# C210_0001_Serial_Interface_220601.net
KiCad netlist of a schematic drawn in Altium Designer
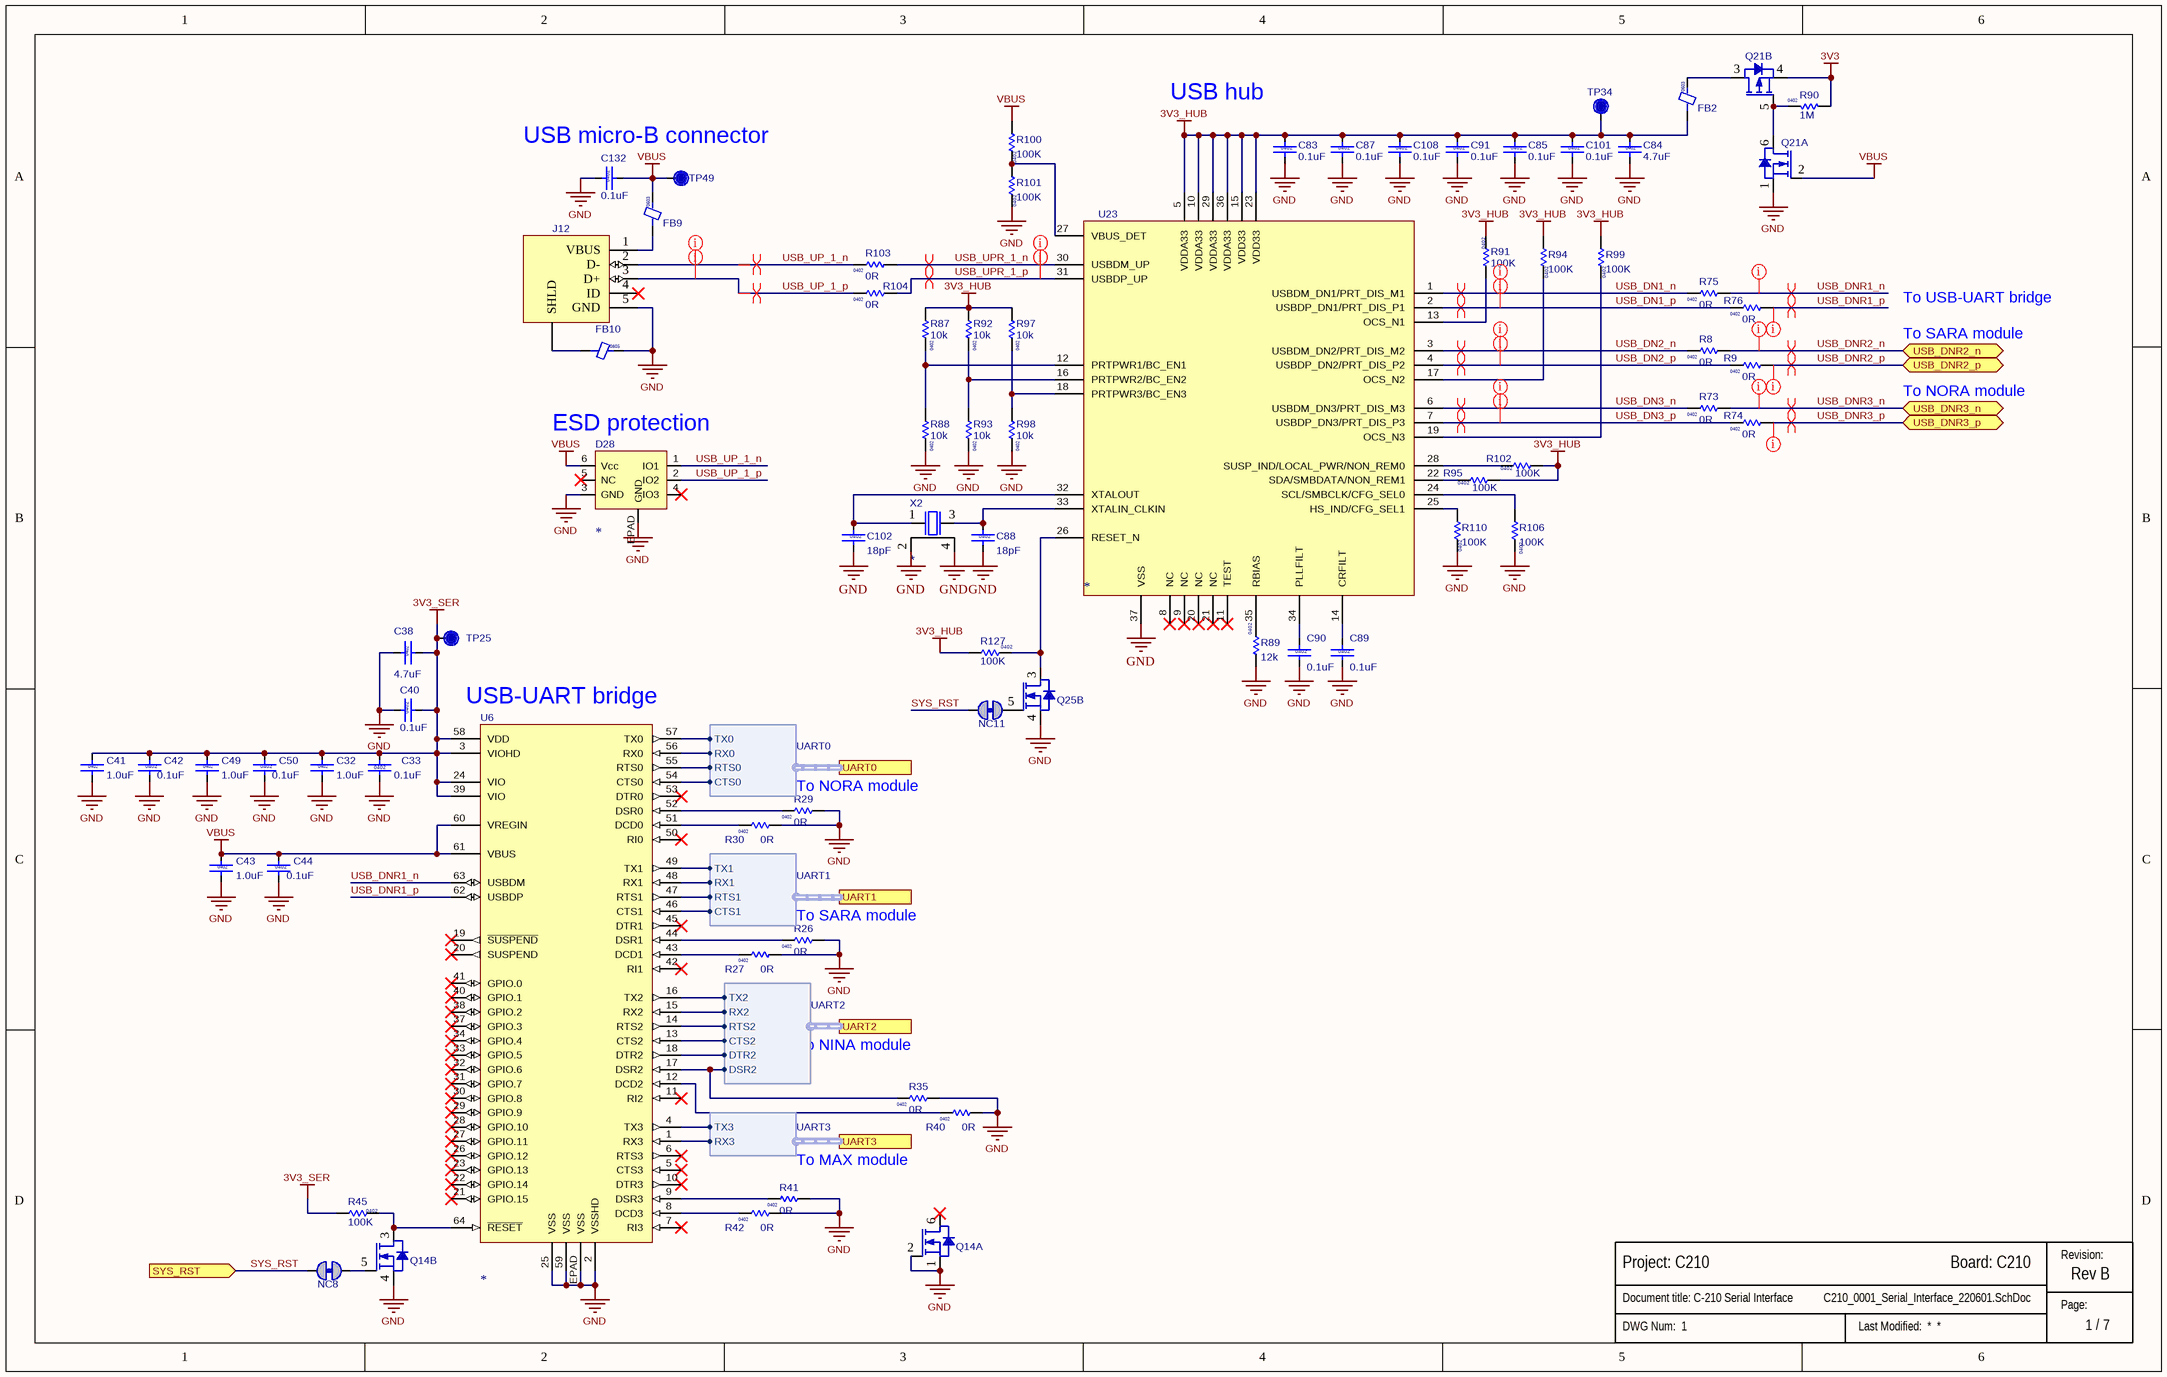
[diagram p0: C210_0001_Serial_Interface_220601.SchDoc]

(export (version "E")
  (design (tool "Eeschema 10.0.6"))
  (components
    (comp (ref "C32")
      (value "1.0uF")
      (footprint "Cap 0402 HD")
      (description "Cap, Ceramic, 1.0uF 10V 10% X5R, 0402")
      (fields
        (field (name "SIZE") "0402")
        (field (name "PART NUMBER") "120-00017")
        (field (name "MANUFACTURER") "Murata Electronics North America")
      )
      (libsource (lib "Arena_Parts_DB_Lib") (part "Cap Chip"))
    )
    (comp (ref "C33")
      (value "0.1uF")
      (footprint "Cap 0402 HD")
      (description "Cap, Ceramic 0.1uF 10V 10% X5R 0402")
      (fields
        (field (name "SIZE") "0402")
        (field (name "PART NUMBER") "120-00016")
        (field (name "MANUFACTURER") "Murata Electronics North America")
      )
      (libsource (lib "Arena_Parts_DB_Lib") (part "Cap Chip"))
    )
    (comp (ref "C38")
      (value "4.7uF")
      (footprint "Cap 0402 HD")
      (description "Cap, Ceramic 4.7uF 10V 20% X5R 0402")
      (fields
        (field (name "SIZE") "0402")
        (field (name "PART NUMBER") "120-00020")
        (field (name "TOLERANCE") "+/- 20%")
      )
      (libsource (lib "Arena_Parts_DB_Lib") (part "Cap Chip"))
    )
    (comp (ref "C40")
      (value "0.1uF")
      (footprint "Cap 0402 HD")
      (description "Cap, Ceramic 0.1uF 10V 10% X5R 0402")
      (fields
        (field (name "SIZE") "0402")
        (field (name "PART NUMBER") "120-00016")
        (field (name "MANUFACTURER") "Murata Electronics North America")
      )
      (libsource (lib "Arena_Parts_DB_Lib") (part "Cap Chip"))
    )
    (comp (ref "C41")
      (value "1.0uF")
      (footprint "Cap 0402 HD")
      (description "Cap, Ceramic, 1.0uF 10V 10% X5R, 0402")
      (fields
        (field (name "SIZE") "0402")
        (field (name "PART NUMBER") "120-00017")
        (field (name "MANUFACTURER") "Murata Electronics North America")
      )
      (libsource (lib "Arena_Parts_DB_Lib") (part "Cap Chip"))
    )
    (comp (ref "C42")
      (value "0.1uF")
      (footprint "Cap 0402 HD")
      (description "Cap, Ceramic 0.1uF 10V 10% X5R 0402")
      (fields
        (field (name "SIZE") "0402")
        (field (name "PART NUMBER") "120-00016")
        (field (name "MANUFACTURER") "Murata Electronics North America")
      )
      (libsource (lib "Arena_Parts_DB_Lib") (part "Cap Chip"))
    )
    (comp (ref "C43")
      (value "1.0uF")
      (footprint "Cap 0402 HD")
      (description "Cap, Ceramic, 1.0uF 10V 10% X5R, 0402")
      (fields
        (field (name "SIZE") "0402")
        (field (name "PART NUMBER") "120-00017")
        (field (name "MANUFACTURER") "Murata Electronics North America")
      )
      (libsource (lib "Arena_Parts_DB_Lib") (part "Cap Chip"))
    )
    (comp (ref "C44")
      (value "0.1uF")
      (footprint "Cap 0402 HD")
      (description "Cap, Ceramic 0.1uF 10V 10% X5R 0402")
      (fields
        (field (name "SIZE") "0402")
        (field (name "PART NUMBER") "120-00016")
        (field (name "MANUFACTURER") "Murata Electronics North America")
      )
      (libsource (lib "Arena_Parts_DB_Lib") (part "Cap Chip"))
    )
    (comp (ref "C49")
      (value "1.0uF")
      (footprint "Cap 0402 HD")
      (description "Cap, Ceramic, 1.0uF 10V 10% X5R, 0402")
      (fields
        (field (name "SIZE") "0402")
        (field (name "PART NUMBER") "120-00017")
        (field (name "MANUFACTURER") "Murata Electronics North America")
      )
      (libsource (lib "Arena_Parts_DB_Lib") (part "Cap Chip"))
    )
    (comp (ref "C50")
      (value "0.1uF")
      (footprint "Cap 0402 HD")
      (description "Cap, Ceramic 0.1uF 10V 10% X5R 0402")
      (fields
        (field (name "SIZE") "0402")
        (field (name "PART NUMBER") "120-00016")
        (field (name "MANUFACTURER") "Murata Electronics North America")
      )
      (libsource (lib "Arena_Parts_DB_Lib") (part "Cap Chip"))
    )
    (comp (ref "C83")
      (value "0.1uF")
      (footprint "Cap 0402 HD")
      (description "Cap, Ceramic 0.1uF 10V 10% X5R 0402")
      (fields
        (field (name "SIZE") "0402")
        (field (name "PART NUMBER") "120-00016")
        (field (name "MANUFACTURER") "Murata Electronics North America")
      )
      (libsource (lib "Arena_Parts_DB_Lib") (part "Cap Chip"))
    )
    (comp (ref "C84")
      (value "4.7uF")
      (footprint "Cap 0402 HD")
      (description "Cap, Ceramic 4.7uF 10V 20% X5R 0402")
      (fields
        (field (name "SIZE") "0402")
        (field (name "PART NUMBER") "120-00020")
        (field (name "TOLERANCE") "+/- 20%")
      )
      (libsource (lib "Arena_Parts_DB_Lib") (part "Cap Chip"))
    )
    (comp (ref "C85")
      (value "0.1uF")
      (footprint "Cap 0402 HD")
      (description "Cap, Ceramic 0.1uF 10V 10% X5R 0402")
      (fields
        (field (name "SIZE") "0402")
        (field (name "PART NUMBER") "120-00016")
        (field (name "MANUFACTURER") "Murata Electronics North America")
      )
      (libsource (lib "Arena_Parts_DB_Lib") (part "Cap Chip"))
    )
    (comp (ref "C87")
      (value "0.1uF")
      (footprint "Cap 0402 HD")
      (description "Cap, Ceramic 0.1uF 10V 10% X5R 0402")
      (fields
        (field (name "SIZE") "0402")
        (field (name "PART NUMBER") "120-00016")
        (field (name "MANUFACTURER") "Murata Electronics North America")
      )
      (libsource (lib "Arena_Parts_DB_Lib") (part "Cap Chip"))
    )
    (comp (ref "C88")
      (value "18pF")
      (footprint "Cap 0402 HD")
      (description "Cap, Ceramic 18pF 50V 5% NP0 0402")
      (fields
        (field (name "SIZE") "0402")
        (field (name "PART NUMBER") "120-00041")
        (field (name "TOLERANCE") "+/- 5%")
      )
      (libsource (lib "Arena_Parts_DB_Lib") (part "Cap Chip"))
    )
    (comp (ref "C89")
      (value "0.1uF")
      (footprint "Cap 0402 HD")
      (description "Cap, Ceramic 0.1uF 10V 10% X5R 0402")
      (fields
        (field (name "SIZE") "0402")
        (field (name "PART NUMBER") "120-00016")
        (field (name "MANUFACTURER") "Murata Electronics North America")
      )
      (libsource (lib "Arena_Parts_DB_Lib") (part "Cap Chip"))
    )
    (comp (ref "C90")
      (value "0.1uF")
      (footprint "Cap 0402 HD")
      (description "Cap, Ceramic 0.1uF 10V 10% X5R 0402")
      (fields
        (field (name "SIZE") "0402")
        (field (name "PART NUMBER") "120-00016")
        (field (name "MANUFACTURER") "Murata Electronics North America")
      )
      (libsource (lib "Arena_Parts_DB_Lib") (part "Cap Chip"))
    )
    (comp (ref "C91")
      (value "0.1uF")
      (footprint "Cap 0402 HD")
      (description "Cap, Ceramic 0.1uF 10V 10% X5R 0402")
      (fields
        (field (name "SIZE") "0402")
        (field (name "PART NUMBER") "120-00016")
        (field (name "MANUFACTURER") "Murata Electronics North America")
      )
      (libsource (lib "Arena_Parts_DB_Lib") (part "Cap Chip"))
    )
    (comp (ref "C101")
      (value "0.1uF")
      (footprint "Cap 0402 HD")
      (description "Cap, Ceramic 0.1uF 10V 10% X5R 0402")
      (fields
        (field (name "SIZE") "0402")
        (field (name "PART NUMBER") "120-00016")
        (field (name "MANUFACTURER") "Murata Electronics North America")
      )
      (libsource (lib "Arena_Parts_DB_Lib") (part "Cap Chip"))
    )
    (comp (ref "C102")
      (value "18pF")
      (footprint "Cap 0402 HD")
      (description "Cap, Ceramic 18pF 50V 5% NP0 0402")
      (fields
        (field (name "SIZE") "0402")
        (field (name "PART NUMBER") "120-00041")
        (field (name "TOLERANCE") "+/- 5%")
      )
      (libsource (lib "Arena_Parts_DB_Lib") (part "Cap Chip"))
    )
    (comp (ref "C108")
      (value "0.1uF")
      (footprint "Cap 0402 HD")
      (description "Cap, Ceramic 0.1uF 10V 10% X5R 0402")
      (fields
        (field (name "SIZE") "0402")
        (field (name "PART NUMBER") "120-00016")
        (field (name "MANUFACTURER") "Murata Electronics North America")
      )
      (libsource (lib "Arena_Parts_DB_Lib") (part "Cap Chip"))
    )
    (comp (ref "C132")
      (value "0.1uF")
      (footprint "Cap 0402 HD")
      (description "Cap, Ceramic 0.1uF 10V 10% X5R 0402")
      (fields
        (field (name "SIZE") "0402")
        (field (name "PART NUMBER") "120-00016")
        (field (name "MANUFACTURER") "Murata Electronics North America")
      )
      (libsource (lib "Arena_Parts_DB_Lib") (part "Cap Chip"))
    )
    (comp (ref "D28")
      (value "~")
      (footprint "TPD3E001DRSR")
      (description "TVS Diode, ESD High Speed 3-Channel Array, WSON-6, 3mmX3mm")
      (fields (field (name "VOLTAGE") "5.5V") (field (name "MANUFACTURER P/N") "*"))
      (libsource (lib "TPD3E001DRSR") (part "TPD3E001"))
    )
    (comp (ref "FB2")
      (value "BLM18EG221SN1")
      (footprint "BLM18EG221SN1")
      (description "Ferrite Bead, 220ohm @ 100MHz, 2A, 0603")
      (fields (field (name "VOLTAGE") "None") (field (name "SIZE") "0603"))
      (libsource (lib "BLM18EG221SN1") (part "BLM18EG221SN1"))
    )
    (comp (ref "FB9")
      (value "BLM18EG221SN1")
      (footprint "BLM18EG221SN1")
      (description "Ferrite Bead, 220ohm @ 100MHz, 2A, 0603")
      (fields (field (name "VOLTAGE") "None") (field (name "SIZE") "0603"))
      (libsource (lib "BLM18EG221SN1") (part "BLM18EG221SN1"))
    )
    (comp (ref "FB10")
      (value "155-00014")
      (footprint "IND 0805")
      (description "Ferrite Bead, 120ohm @ 100MHz, 3A, 0805")
      (fields (field (name "SIZE") "0805") (field (name "VOLTAGE") "None"))
      (libsource (lib "Arena_Parts_DB_Lib") (part "FB sm"))
    )
    (comp (ref "J12")
      (value "130-00008")
      (footprint "USB_Micro_RA_W-2TABS")
      (description "USB Micro B Receptacle, Right Angle SMT with 2 TH Tabs, 0.65mm")
      (fields (field (name "MANUFACTURER") "FCI"))
      (libsource (lib "Arena_Lib") (part "USB_W-Shield"))
    )
    (comp (ref "NC8")
      (value "Solderbridge-ShortDNP")
      (footprint "Solderbridge-Short")
      (description "Solderbridge-Short")
      (fields (field (name "ADDED BY") "Paul B"))
      (libsource (lib "PCB_Misc") (part "Solderbridge-Short"))
    )
    (comp (ref "NC11")
      (value "Solderbridge-ShortDNP")
      (footprint "Solderbridge-Short")
      (description "Solderbridge-Short")
      (fields (field (name "ADDED BY") "Paul B"))
      (libsource (lib "PCB_Misc") (part "Solderbridge-Short"))
    )
    (comp (ref "Q14")
      (value "140-00016")
      (footprint "SOT-563")
      (description "MOSFET 2N-CH 20V 0.8A, SOT-563")
      (fields (field (name "VOLTAGE") "20V"))
      (libsource (lib "Arena_Parts_DB_Lib") (part "MOSFET-N-Dual"))
    )
    (comp (ref "Q21")
      (value "140-00030")
      (footprint "SOT-563")
      (description "MOSFET N/P-CH 20V SOT-563, 540 mA, −430 mA")
      (fields (field (name "VOLTAGE") "20V"))
      (libsource (lib "Arena_Parts_DB_Lib") (part "MOSFET-N-P_Pair"))
    )
    (comp (ref "Q25")
      (value "140-00016")
      (footprint "SOT-563")
      (description "MOSFET 2N-CH 20V 0.8A, SOT-563")
      (fields (field (name "VOLTAGE") "20V"))
      (libsource (lib "Arena_Parts_DB_Lib") (part "MOSFET-N-Dual"))
    )
    (comp (ref "R8")
      (value "0R")
      (footprint "RES 0402 HD")
      (description "Resistor 0 ohm 1/16W 0402")
      (fields
        (field (name "SIZE") "0402")
        (field (name "PART NUMBER") "180-00020")
        (field (name "POWER") "1/16W")
      )
      (libsource (lib "Arena_Parts_DB_Lib") (part "Res sm"))
    )
    (comp (ref "R9")
      (value "0R")
      (footprint "RES 0402 HD")
      (description "Resistor 0 ohm 1/16W 0402")
      (fields
        (field (name "SIZE") "0402")
        (field (name "PART NUMBER") "180-00020")
        (field (name "POWER") "1/16W")
      )
      (libsource (lib "Arena_Parts_DB_Lib") (part "Res sm"))
    )
    (comp (ref "R26")
      (value "0R")
      (footprint "RES 0402 HD")
      (description "Resistor 0 ohm 1/16W 0402")
      (fields
        (field (name "SIZE") "0402")
        (field (name "PART NUMBER") "180-00020")
        (field (name "POWER") "1/16W")
      )
      (libsource (lib "Arena_Parts_DB_Lib") (part "Res sm"))
    )
    (comp (ref "R27")
      (value "0R")
      (footprint "RES 0402 HD")
      (description "Resistor 0 ohm 1/16W 0402")
      (fields
        (field (name "SIZE") "0402")
        (field (name "PART NUMBER") "180-00020")
        (field (name "POWER") "1/16W")
      )
      (libsource (lib "Arena_Parts_DB_Lib") (part "Res sm"))
    )
    (comp (ref "R29")
      (value "0R")
      (footprint "RES 0402 HD")
      (description "Resistor 0 ohm 1/16W 0402")
      (fields
        (field (name "SIZE") "0402")
        (field (name "PART NUMBER") "180-00020")
        (field (name "POWER") "1/16W")
      )
      (libsource (lib "Arena_Parts_DB_Lib") (part "Res sm"))
    )
    (comp (ref "R30")
      (value "0R")
      (footprint "RES 0402 HD")
      (description "Resistor 0 ohm 1/16W 0402")
      (fields
        (field (name "SIZE") "0402")
        (field (name "PART NUMBER") "180-00020")
        (field (name "POWER") "1/16W")
      )
      (libsource (lib "Arena_Parts_DB_Lib") (part "Res sm"))
    )
    (comp (ref "R35")
      (value "0R")
      (footprint "RES 0402 HD")
      (description "Resistor 0 ohm 1/16W 0402")
      (fields
        (field (name "SIZE") "0402")
        (field (name "PART NUMBER") "180-00020")
        (field (name "POWER") "1/16W")
      )
      (libsource (lib "Arena_Parts_DB_Lib") (part "Res sm"))
    )
    (comp (ref "R40")
      (value "0R")
      (footprint "RES 0402 HD")
      (description "Resistor 0 ohm 1/16W 0402")
      (fields
        (field (name "SIZE") "0402")
        (field (name "PART NUMBER") "180-00020")
        (field (name "POWER") "1/16W")
      )
      (libsource (lib "Arena_Parts_DB_Lib") (part "Res sm"))
    )
    (comp (ref "R41")
      (value "0R")
      (footprint "RES 0402 HD")
      (description "Resistor 0 ohm 1/16W 0402")
      (fields
        (field (name "SIZE") "0402")
        (field (name "PART NUMBER") "180-00020")
        (field (name "POWER") "1/16W")
      )
      (libsource (lib "Arena_Parts_DB_Lib") (part "Res sm"))
    )
    (comp (ref "R42")
      (value "0R")
      (footprint "RES 0402 HD")
      (description "Resistor 0 ohm 1/16W 0402")
      (fields
        (field (name "SIZE") "0402")
        (field (name "PART NUMBER") "180-00020")
        (field (name "POWER") "1/16W")
      )
      (libsource (lib "Arena_Parts_DB_Lib") (part "Res sm"))
    )
    (comp (ref "R45")
      (value "100K")
      (footprint "RES 0402 HD")
      (description "Resistor 100K ohm 1% 1/16W, 0402")
      (fields
        (field (name "SIZE") "0402")
        (field (name "PART NUMBER") "180-00093")
        (field (name "POWER") "1/16W")
      )
      (libsource (lib "Arena_Parts_DB_Lib") (part "Res sm"))
    )
    (comp (ref "R73")
      (value "0R")
      (footprint "RES 0402 HD")
      (description "Resistor 0 ohm 1/16W 0402")
      (fields
        (field (name "SIZE") "0402")
        (field (name "PART NUMBER") "180-00020")
        (field (name "POWER") "1/16W")
      )
      (libsource (lib "Arena_Parts_DB_Lib") (part "Res sm"))
    )
    (comp (ref "R74")
      (value "0R")
      (footprint "RES 0402 HD")
      (description "Resistor 0 ohm 1/16W 0402")
      (fields
        (field (name "SIZE") "0402")
        (field (name "PART NUMBER") "180-00020")
        (field (name "POWER") "1/16W")
      )
      (libsource (lib "Arena_Parts_DB_Lib") (part "Res sm"))
    )
    (comp (ref "R75")
      (value "0R")
      (footprint "RES 0402 HD")
      (description "Resistor 0 ohm 1/16W 0402")
      (fields
        (field (name "SIZE") "0402")
        (field (name "PART NUMBER") "180-00020")
        (field (name "POWER") "1/16W")
      )
      (libsource (lib "Arena_Parts_DB_Lib") (part "Res sm"))
    )
    (comp (ref "R76")
      (value "0R")
      (footprint "RES 0402 HD")
      (description "Resistor 0 ohm 1/16W 0402")
      (fields
        (field (name "SIZE") "0402")
        (field (name "PART NUMBER") "180-00020")
        (field (name "POWER") "1/16W")
      )
      (libsource (lib "Arena_Parts_DB_Lib") (part "Res sm"))
    )
    (comp (ref "R87")
      (value "10k")
      (footprint "RES 0402 HD")
      (description "Resistor 10k ohm 1% 1/16W, 0402")
      (fields
        (field (name "SIZE") "0402")
        (field (name "PART NUMBER") "180-00024")
        (field (name "POWER") "1/16W")
      )
      (libsource (lib "Arena_Parts_DB_Lib") (part "Res sm"))
    )
    (comp (ref "R88")
      (value "10k")
      (footprint "RES 0402 HD")
      (description "Resistor 10k ohm 1% 1/16W, 0402")
      (fields
        (field (name "SIZE") "0402")
        (field (name "PART NUMBER") "180-00024")
        (field (name "POWER") "1/16W")
      )
      (libsource (lib "Arena_Parts_DB_Lib") (part "Res sm"))
    )
    (comp (ref "R89")
      (value "12k")
      (footprint "RES 0402 HD")
      (description "Resistor 12k ohm 1% 1/16W 0402")
      (fields
        (field (name "SIZE") "0402")
        (field (name "PART NUMBER") "180-00096")
        (field (name "POWER") "1/16W")
      )
      (libsource (lib "Arena_Parts_DB_Lib") (part "Res sm"))
    )
    (comp (ref "R90")
      (value "1M")
      (footprint "RES 0402 HD")
      (description "Resistor 1M ohm 1%, 1/16W, 0402")
      (fields
        (field (name "SIZE") "0402")
        (field (name "PART NUMBER") "180-00054")
        (field (name "POWER") "1/16W")
      )
      (libsource (lib "Arena_Parts_DB_Lib") (part "Res sm"))
    )
    (comp (ref "R91")
      (value "100K")
      (footprint "RES 0402 HD")
      (description "Resistor 100K ohm 1% 1/16W, 0402")
      (fields
        (field (name "SIZE") "0402")
        (field (name "PART NUMBER") "180-00093")
        (field (name "POWER") "1/16W")
      )
      (libsource (lib "Arena_Parts_DB_Lib") (part "Res sm"))
    )
    (comp (ref "R92")
      (value "10k")
      (footprint "RES 0402 HD")
      (description "Resistor 10k ohm 1% 1/16W, 0402")
      (fields
        (field (name "SIZE") "0402")
        (field (name "PART NUMBER") "180-00024")
        (field (name "POWER") "1/16W")
      )
      (libsource (lib "Arena_Parts_DB_Lib") (part "Res sm"))
    )
    (comp (ref "R93")
      (value "10k")
      (footprint "RES 0402 HD")
      (description "Resistor 10k ohm 1% 1/16W, 0402")
      (fields
        (field (name "SIZE") "0402")
        (field (name "PART NUMBER") "180-00024")
        (field (name "POWER") "1/16W")
      )
      (libsource (lib "Arena_Parts_DB_Lib") (part "Res sm"))
    )
    (comp (ref "R94")
      (value "100K")
      (footprint "RES 0402 HD")
      (description "Resistor 100K ohm 1% 1/16W, 0402")
      (fields
        (field (name "SIZE") "0402")
        (field (name "PART NUMBER") "180-00093")
        (field (name "POWER") "1/16W")
      )
      (libsource (lib "Arena_Parts_DB_Lib") (part "Res sm"))
    )
    (comp (ref "R95")
      (value "100K")
      (footprint "RES 0402 HD")
      (description "Resistor 100K ohm 1% 1/16W, 0402")
      (fields
        (field (name "SIZE") "0402")
        (field (name "PART NUMBER") "180-00093")
        (field (name "POWER") "1/16W")
      )
      (libsource (lib "Arena_Parts_DB_Lib") (part "Res sm"))
    )
    (comp (ref "R97")
      (value "10k")
      (footprint "RES 0402 HD")
      (description "Resistor 10k ohm 1% 1/16W, 0402")
      (fields
        (field (name "SIZE") "0402")
        (field (name "PART NUMBER") "180-00024")
        (field (name "POWER") "1/16W")
      )
      (libsource (lib "Arena_Parts_DB_Lib") (part "Res sm"))
    )
    (comp (ref "R98")
      (value "10k")
      (footprint "RES 0402 HD")
      (description "Resistor 10k ohm 1% 1/16W, 0402")
      (fields
        (field (name "SIZE") "0402")
        (field (name "PART NUMBER") "180-00024")
        (field (name "POWER") "1/16W")
      )
      (libsource (lib "Arena_Parts_DB_Lib") (part "Res sm"))
    )
    (comp (ref "R99")
      (value "100K")
      (footprint "RES 0402 HD")
      (description "Resistor 100K ohm 1% 1/16W, 0402")
      (fields
        (field (name "SIZE") "0402")
        (field (name "PART NUMBER") "180-00093")
        (field (name "POWER") "1/16W")
      )
      (libsource (lib "Arena_Parts_DB_Lib") (part "Res sm"))
    )
    (comp (ref "R100")
      (value "100K")
      (footprint "RES 0402 HD")
      (description "Resistor 100K ohm 1% 1/16W, 0402")
      (fields
        (field (name "SIZE") "0402")
        (field (name "PART NUMBER") "180-00093")
        (field (name "POWER") "1/16W")
      )
      (libsource (lib "Arena_Parts_DB_Lib") (part "Res sm"))
    )
    (comp (ref "R101")
      (value "100K")
      (footprint "RES 0402 HD")
      (description "Resistor 100K ohm 1% 1/16W, 0402")
      (fields
        (field (name "SIZE") "0402")
        (field (name "PART NUMBER") "180-00093")
        (field (name "POWER") "1/16W")
      )
      (libsource (lib "Arena_Parts_DB_Lib") (part "Res sm"))
    )
    (comp (ref "R102")
      (value "100K")
      (footprint "RES 0402 HD")
      (description "Resistor 100K ohm 1% 1/16W, 0402")
      (fields
        (field (name "SIZE") "0402")
        (field (name "PART NUMBER") "180-00093")
        (field (name "POWER") "1/16W")
      )
      (libsource (lib "Arena_Parts_DB_Lib") (part "Res sm"))
    )
    (comp (ref "R103")
      (value "0R")
      (footprint "RES 0402 HD")
      (description "Resistor 0 ohm 1/16W 0402")
      (fields
        (field (name "SIZE") "0402")
        (field (name "PART NUMBER") "180-00020")
        (field (name "POWER") "1/16W")
      )
      (libsource (lib "Arena_Parts_DB_Lib") (part "Res sm"))
    )
    (comp (ref "R104")
      (value "0R")
      (footprint "RES 0402 HD")
      (description "Resistor 0 ohm 1/16W 0402")
      (fields
        (field (name "SIZE") "0402")
        (field (name "PART NUMBER") "180-00020")
        (field (name "POWER") "1/16W")
      )
      (libsource (lib "Arena_Parts_DB_Lib") (part "Res sm"))
    )
    (comp (ref "R106")
      (value "100K")
      (footprint "RES 0402 HD")
      (description "Resistor 100K ohm 1% 1/16W, 0402")
      (fields
        (field (name "SIZE") "0402")
        (field (name "PART NUMBER") "180-00093")
        (field (name "POWER") "1/16W")
      )
      (libsource (lib "Arena_Parts_DB_Lib") (part "Res sm"))
    )
    (comp (ref "R110")
      (value "100K")
      (footprint "RES 0402 HD")
      (description "Resistor 100K ohm 1% 1/16W, 0402")
      (fields
        (field (name "SIZE") "0402")
        (field (name "PART NUMBER") "180-00093")
        (field (name "POWER") "1/16W")
      )
      (libsource (lib "Arena_Parts_DB_Lib") (part "Res sm"))
    )
    (comp (ref "R127")
      (value "100K")
      (footprint "RES 0402 HD")
      (description "Resistor 100K ohm 1% 1/16W, 0402")
      (fields
        (field (name "SIZE") "0402")
        (field (name "PART NUMBER") "180-00093")
        (field (name "POWER") "1/16W")
      )
      (libsource (lib "Arena_Parts_DB_Lib") (part "Res sm"))
    )
    (comp (ref "TP25")
      (value "TP")
      (footprint "TP12R")
      (description "Testpoint, Round 1.0mm Dia")
      (fields
        (field (name "PART NUMBER") "TP10R")
        (field (name "ADDED BY") "Jeremy D")
        (field (name "CHECKED BY") "Paul B")
      )
      (libsource (lib "PCB_Misc") (part "TP_R"))
    )
    (comp (ref "TP34")
      (value "TP")
      (footprint "TP12R")
      (description "Testpoint, Round 1.0mm Dia")
      (fields
        (field (name "PART NUMBER") "TP10R")
        (field (name "ADDED BY") "Jeremy D")
        (field (name "CHECKED BY") "Paul B")
      )
      (libsource (lib "PCB_Misc") (part "TP_R"))
    )
    (comp (ref "TP49")
      (value "TP")
      (footprint "TP12R")
      (description "Testpoint, Round 1.0mm Dia")
      (fields
        (field (name "PART NUMBER") "TP10R")
        (field (name "ADDED BY") "Jeremy D")
        (field (name "CHECKED BY") "Paul B")
      )
      (libsource (lib "PCB_Misc") (part "TP_R"))
    )
    (comp (ref "U6")
      (value "220-00051")
      (footprint "QFN0.5P16x16-64Pin_W-Pad4.25mm")
      (description "IC BRIDGE USB TO UART 64QFN")
      (fields (field (name "MANUFACTURER P/N") "*") (field (name "VOLTAGE") "3.6V"))
      (libsource (lib "Arena_Parts_DB_Lib") (part "CP2108"))
    )
    (comp (ref "U23")
      (value "-\"Part Number\" + DNP")
      (footprint "QFN0.5P9x9-36Pin_W-PAD")
      (description "3-PORT USB 2.0 HUB CTRLR, QFN-36")
      (fields
        (field (name "MANUFACTURER P/N") "*")
        (field (name "PART NUMBER") "220-00017")
        (field (name "VOLTAGE") "3.6V")
      )
      (libsource (lib "Arena_Parts_DB_Lib") (part "USB2513B"))
    )
    (comp (ref "X2")
      (value "100-00017")
      (footprint "XTAL_2520_HD")
      (description "Crystal, 24.0000MHz, 20ppm, 10pF, 100 Ohm, -20Â°C - 70Â°C, SMT 4 Pin 2520")
      (fields (field (name "ALTIUM_VALUE") "*") (field (name "VOLTAGE") "None"))
      (libsource (lib "Arena_Parts_DB_Lib") (part "XTAL_4Pin"))
    )
  )
  (nets
    (net (code "5") (name "/CTS0") (class "Default")
      (node (ref "U6") (pin "54") (pinfunction "CTS0_54") (pintype "input"))
    )
    (net (code "6") (name "/CTS1") (class "Default")
      (node (ref "U6") (pin "46") (pinfunction "CTS1_46") (pintype "input"))
    )
    (net (code "7") (name "/CTS2") (class "Default")
      (node (ref "U6") (pin "13") (pinfunction "CTS2_13") (pintype "input"))
    )
    (net (code "8") (name "/DSR2") (class "Default")
      (node (ref "R35") (pin "2") (pinfunction "2_2") (pintype "passive"))
      (node (ref "U6") (pin "17") (pinfunction "DSR2_17") (pintype "input"))
    )
    (net (code "9") (name "/DTR2") (class "Default")
      (node (ref "U6") (pin "18") (pinfunction "DTR2_18") (pintype "output"))
    )
    (net (code "10") (name "/RTS0") (class "Default")
      (node (ref "U6") (pin "55") (pinfunction "RTS0_55") (pintype "output"))
    )
    (net (code "11") (name "/RTS1") (class "Default")
      (node (ref "U6") (pin "47") (pinfunction "RTS1_47") (pintype "output"))
    )
    (net (code "12") (name "/RTS2") (class "Default")
      (node (ref "U6") (pin "14") (pinfunction "RTS2_14") (pintype "output"))
    )
    (net (code "13") (name "/RX0") (class "Default")
      (node (ref "U6") (pin "56") (pinfunction "RX0_56") (pintype "input"))
    )
    (net (code "14") (name "/RX1") (class "Default")
      (node (ref "U6") (pin "48") (pinfunction "RX1_48") (pintype "input"))
    )
    (net (code "15") (name "/RX2") (class "Default")
      (node (ref "U6") (pin "15") (pinfunction "RX2_15") (pintype "input"))
    )
    (net (code "16") (name "/RX3") (class "Default")
      (node (ref "U6") (pin "1") (pinfunction "RX3_1") (pintype "input"))
    )
    (net (code "17") (name "/SYS_RST") (class "Default")
      (node (ref "NC11") (pin "2") (pinfunction "2_2") (pintype "passive"))
      (node (ref "NC8") (pin "2") (pinfunction "2_2") (pintype "passive"))
    )
    (net (code "18") (name "/TX0") (class "Default")
      (node (ref "U6") (pin "57") (pinfunction "TX0_57") (pintype "output"))
    )
    (net (code "19") (name "/TX1") (class "Default")
      (node (ref "U6") (pin "49") (pinfunction "TX1_49") (pintype "output"))
    )
    (net (code "20") (name "/TX2") (class "Default")
      (node (ref "U6") (pin "16") (pinfunction "TX2_16") (pintype "output"))
    )
    (net (code "21") (name "/TX3") (class "Default")
      (node (ref "U6") (pin "4") (pinfunction "TX3_4") (pintype "output"))
    )
    (net (code "22") (name "/USB_DN1_n") (class "Default")
      (node (ref "R75") (pin "2") (pinfunction "2_2") (pintype "passive"))
      (node (ref "U23") (pin "1") (pinfunction "USBDM_DN1/PRT_DIS_M1_1") (pintype "passive"))
    )
    (net (code "23") (name "/USB_DN1_p") (class "Default")
      (node (ref "R76") (pin "2") (pinfunction "2_2") (pintype "passive"))
      (node (ref "U23") (pin "2") (pinfunction "USBDP_DN1/PRT_DIS_P1_2") (pintype "passive"))
    )
    (net (code "24") (name "/USB_DN2_n") (class "Default")
      (node (ref "R8") (pin "2") (pinfunction "2_2") (pintype "passive"))
      (node (ref "U23") (pin "3") (pinfunction "USBDM_DN2/PRT_DIS_M2_3") (pintype "passive"))
    )
    (net (code "25") (name "/USB_DN2_p") (class "Default")
      (node (ref "R9") (pin "2") (pinfunction "2_2") (pintype "passive"))
      (node (ref "U23") (pin "4") (pinfunction "USBDP_DN2/PRT_DIS_P2_4") (pintype "passive"))
    )
    (net (code "26") (name "/USB_DN3_n") (class "Default")
      (node (ref "R73") (pin "2") (pinfunction "2_2") (pintype "passive"))
      (node (ref "U23") (pin "6") (pinfunction "USBDM_DN3/PRT_DIS_M3_6") (pintype "passive"))
    )
    (net (code "27") (name "/USB_DN3_p") (class "Default")
      (node (ref "R74") (pin "2") (pinfunction "2_2") (pintype "passive"))
      (node (ref "U23") (pin "7") (pinfunction "USBDP_DN3/PRT_DIS_P3_7") (pintype "passive"))
    )
    (net (code "28") (name "/USB_DNR1_n") (class "Default")
      (node (ref "R75") (pin "1") (pinfunction "1_1") (pintype "passive"))
      (node (ref "U6") (pin "63") (pinfunction "USBDM_63") (pintype "bidirectional"))
    )
    (net (code "29") (name "/USB_DNR1_p") (class "Default")
      (node (ref "R76") (pin "1") (pinfunction "1_1") (pintype "passive"))
      (node (ref "U6") (pin "62") (pinfunction "USBDP_62") (pintype "bidirectional"))
    )
    (net (code "30") (name "/USB_DNR2_n") (class "Default")
      (node (ref "R8") (pin "1") (pinfunction "1_1") (pintype "passive"))
    )
    (net (code "31") (name "/USB_DNR2_p") (class "Default")
      (node (ref "R9") (pin "1") (pinfunction "1_1") (pintype "passive"))
    )
    (net (code "32") (name "/USB_DNR3_n") (class "Default")
      (node (ref "R73") (pin "1") (pinfunction "1_1") (pintype "passive"))
    )
    (net (code "33") (name "/USB_DNR3_p") (class "Default")
      (node (ref "R74") (pin "1") (pinfunction "1_1") (pintype "passive"))
    )
    (net (code "34") (name "/USB_UPR_1_n") (class "Default")
      (node (ref "R103") (pin "1") (pinfunction "1_1") (pintype "passive"))
      (node (ref "U23") (pin "30") (pinfunction "USBDM_UP_30") (pintype "passive"))
    )
    (net (code "35") (name "/USB_UPR_1_p") (class "Default")
      (node (ref "R104") (pin "1") (pinfunction "1_1") (pintype "passive"))
      (node (ref "U23") (pin "31") (pinfunction "USBDP_UP_31") (pintype "passive"))
    )
    (net (code "36") (name "/USB_UP_1_n") (class "Default")
      (node (ref "D28") (pin "1") (pinfunction "IO1_1") (pintype "passive"))
      (node (ref "J12") (pin "2") (pinfunction "D-_2") (pintype "bidirectional"))
      (node (ref "R103") (pin "2") (pinfunction "2_2") (pintype "passive"))
    )
    (net (code "37") (name "/USB_UP_1_p") (class "Default")
      (node (ref "D28") (pin "2") (pinfunction "IO2_2") (pintype "passive"))
      (node (ref "J12") (pin "3") (pinfunction "D+_3") (pintype "bidirectional"))
      (node (ref "R104") (pin "2") (pinfunction "2_2") (pintype "passive"))
    )
    (net (code "42") (name "3V3") (class "Default")
      (node (ref "Q21") (pin "4") (pinfunction "S2_4") (pintype "passive"))
      (node (ref "R90") (pin "1") (pinfunction "1_1") (pintype "passive"))
    )
    (net (code "43") (name "3V3_HUB") (class "Default")
      (node (ref "C101") (pin "1") (pinfunction "1_1") (pintype "passive"))
      (node (ref "C108") (pin "1") (pinfunction "1_1") (pintype "passive"))
      (node (ref "C83") (pin "1") (pinfunction "1_1") (pintype "passive"))
      (node (ref "C84") (pin "1") (pinfunction "1_1") (pintype "passive"))
      (node (ref "C85") (pin "1") (pinfunction "1_1") (pintype "passive"))
      (node (ref "C87") (pin "1") (pinfunction "1_1") (pintype "passive"))
      (node (ref "C91") (pin "1") (pinfunction "1_1") (pintype "passive"))
      (node (ref "FB2") (pin "1") (pinfunction "1_1") (pintype "passive"))
      (node (ref "R102") (pin "1") (pinfunction "1_1") (pintype "passive"))
      (node (ref "R127") (pin "1") (pinfunction "1_1") (pintype "passive"))
      (node (ref "R87") (pin "1") (pinfunction "1_1") (pintype "passive"))
      (node (ref "R91") (pin "2") (pinfunction "2_2") (pintype "passive"))
      (node (ref "R92") (pin "1") (pinfunction "1_1") (pintype "passive"))
      (node (ref "R94") (pin "1") (pinfunction "1_1") (pintype "passive"))
      (node (ref "R95") (pin "1") (pinfunction "1_1") (pintype "passive"))
      (node (ref "R97") (pin "1") (pinfunction "1_1") (pintype "passive"))
      (node (ref "R99") (pin "1") (pinfunction "1_1") (pintype "passive"))
      (node (ref "TP34") (pin "1") (pintype "passive"))
      (node (ref "U23") (pin "10") (pinfunction "VDDA33_10") (pintype "passive"))
      (node (ref "U23") (pin "15") (pinfunction "VDD33_15") (pintype "passive"))
      (node (ref "U23") (pin "23") (pinfunction "VDD33_23") (pintype "passive"))
      (node (ref "U23") (pin "29") (pinfunction "VDDA33_29") (pintype "passive"))
      (node (ref "U23") (pin "36") (pinfunction "VDDA33_36") (pintype "passive"))
      (node (ref "U23") (pin "5") (pinfunction "VDDA33_5") (pintype "passive"))
    )
    (net (code "44") (name "3V3_SER") (class "Default")
      (node (ref "C32") (pin "1") (pinfunction "1_1") (pintype "passive"))
      (node (ref "C33") (pin "1") (pinfunction "1_1") (pintype "passive"))
      (node (ref "C38") (pin "2") (pinfunction "2_2") (pintype "passive"))
      (node (ref "C40") (pin "2") (pinfunction "2_2") (pintype "passive"))
      (node (ref "C41") (pin "1") (pinfunction "1_1") (pintype "passive"))
      (node (ref "C42") (pin "1") (pinfunction "1_1") (pintype "passive"))
      (node (ref "C49") (pin "1") (pinfunction "1_1") (pintype "passive"))
      (node (ref "C50") (pin "1") (pinfunction "1_1") (pintype "passive"))
      (node (ref "R45") (pin "1") (pinfunction "1_1") (pintype "passive"))
      (node (ref "TP25") (pin "1") (pintype "passive"))
      (node (ref "U6") (pin "24") (pinfunction "VIO_24") (pintype "power_in"))
      (node (ref "U6") (pin "3") (pinfunction "VIOHD_3") (pintype "power_in"))
      (node (ref "U6") (pin "39") (pinfunction "VIO_39") (pintype "power_in"))
      (node (ref "U6") (pin "58") (pinfunction "VDD_58") (pintype "power_in"))
    )
    (net (code "45") (name "GND") (class "Default")
      (node (ref "C101") (pin "2") (pinfunction "2_2") (pintype "passive"))
      (node (ref "C102") (pin "2") (pinfunction "2_2") (pintype "passive"))
      (node (ref "C108") (pin "2") (pinfunction "2_2") (pintype "passive"))
      (node (ref "C132") (pin "1") (pinfunction "1_1") (pintype "passive"))
      (node (ref "C32") (pin "2") (pinfunction "2_2") (pintype "passive"))
      (node (ref "C33") (pin "2") (pinfunction "2_2") (pintype "passive"))
      (node (ref "C38") (pin "1") (pinfunction "1_1") (pintype "passive"))
      (node (ref "C40") (pin "1") (pinfunction "1_1") (pintype "passive"))
      (node (ref "C41") (pin "2") (pinfunction "2_2") (pintype "passive"))
      (node (ref "C42") (pin "2") (pinfunction "2_2") (pintype "passive"))
      (node (ref "C43") (pin "2") (pinfunction "2_2") (pintype "passive"))
      (node (ref "C44") (pin "2") (pinfunction "2_2") (pintype "passive"))
      (node (ref "C49") (pin "2") (pinfunction "2_2") (pintype "passive"))
      (node (ref "C50") (pin "2") (pinfunction "2_2") (pintype "passive"))
      (node (ref "C83") (pin "2") (pinfunction "2_2") (pintype "passive"))
      (node (ref "C84") (pin "2") (pinfunction "2_2") (pintype "passive"))
      (node (ref "C85") (pin "2") (pinfunction "2_2") (pintype "passive"))
      (node (ref "C87") (pin "2") (pinfunction "2_2") (pintype "passive"))
      (node (ref "C88") (pin "2") (pinfunction "2_2") (pintype "passive"))
      (node (ref "C89") (pin "2") (pinfunction "2_2") (pintype "passive"))
      (node (ref "C90") (pin "2") (pinfunction "2_2") (pintype "passive"))
      (node (ref "C91") (pin "2") (pinfunction "2_2") (pintype "passive"))
      (node (ref "D28") (pin "3") (pinfunction "GND_3") (pintype "power_in"))
      (node (ref "D28") (pin "EPAD") (pinfunction "GND_EPAD") (pintype "power_in"))
      (node (ref "FB10") (pin "2") (pinfunction "2_2") (pintype "passive"))
      (node (ref "J12") (pin "5") (pinfunction "GND_5") (pintype "power_in"))
      (node (ref "Q14") (pin "1") (pinfunction "S1_1") (pintype "passive"))
      (node (ref "Q14") (pin "2") (pinfunction "G1_2") (pintype "passive"))
      (node (ref "Q14") (pin "4") (pinfunction "S2_4") (pintype "passive"))
      (node (ref "Q21") (pin "1") (pinfunction "S1_1") (pintype "passive"))
      (node (ref "Q25") (pin "4") (pinfunction "S2_4") (pintype "passive"))
      (node (ref "R101") (pin "2") (pinfunction "2_2") (pintype "passive"))
      (node (ref "R106") (pin "2") (pinfunction "2_2") (pintype "passive"))
      (node (ref "R110") (pin "2") (pinfunction "2_2") (pintype "passive"))
      (node (ref "R26") (pin "1") (pinfunction "1_1") (pintype "passive"))
      (node (ref "R27") (pin "1") (pinfunction "1_1") (pintype "passive"))
      (node (ref "R29") (pin "1") (pinfunction "1_1") (pintype "passive"))
      (node (ref "R30") (pin "1") (pinfunction "1_1") (pintype "passive"))
      (node (ref "R35") (pin "1") (pinfunction "1_1") (pintype "passive"))
      (node (ref "R40") (pin "1") (pinfunction "1_1") (pintype "passive"))
      (node (ref "R41") (pin "1") (pinfunction "1_1") (pintype "passive"))
      (node (ref "R42") (pin "1") (pinfunction "1_1") (pintype "passive"))
      (node (ref "R88") (pin "2") (pinfunction "2_2") (pintype "passive"))
      (node (ref "R89") (pin "1") (pinfunction "1_1") (pintype "passive"))
      (node (ref "R93") (pin "2") (pinfunction "2_2") (pintype "passive"))
      (node (ref "R98") (pin "2") (pinfunction "2_2") (pintype "passive"))
      (node (ref "U23") (pin "37") (pinfunction "VSS_37") (pintype "power_in"))
      (node (ref "U6") (pin "2") (pinfunction "VSSHD_2") (pintype "power_in"))
      (node (ref "U6") (pin "25") (pinfunction "VSS_25") (pintype "power_in"))
      (node (ref "U6") (pin "59") (pinfunction "VSS_59") (pintype "power_in"))
      (node (ref "U6") (pin "EPAD") (pinfunction "VSS_EPAD") (pintype "power_in"))
      (node (ref "X2") (pin "2") (pintype "passive"))
      (node (ref "X2") (pin "4") (pintype "passive"))
    )
    (net (code "46") (name "Net-(J12-SHLD)") (class "Default")
      (node (ref "FB10") (pin "1") (pinfunction "1_1") (pintype "passive"))
      (node (ref "J12") (pin "6") (pinfunction "SHLD_6") (pintype "passive"))
    )
    (net (code "47") (name "Net-(J12-VBUS)") (class "Default")
      (node (ref "FB9") (pin "1") (pinfunction "1_1") (pintype "passive"))
      (node (ref "J12") (pin "1") (pinfunction "VBUS_1") (pintype "power_in"))
    )
    (net (code "48") (name "Net-(Q14B-D2)") (class "Default")
      (node (ref "Q14") (pin "3") (pinfunction "D2_3") (pintype "passive"))
      (node (ref "R45") (pin "2") (pinfunction "2_2") (pintype "passive"))
      (node (ref "U6") (pin "64") (pinfunction "RESET_64") (pintype "input"))
    )
    (net (code "49") (name "Net-(Q14B-G2)") (class "Default")
      (node (ref "NC8") (pin "1") (pinfunction "1_1") (pintype "passive"))
      (node (ref "Q14") (pin "5") (pinfunction "G2_5") (pintype "passive"))
    )
    (net (code "50") (name "Net-(Q21A-D1)") (class "Default")
      (node (ref "Q21") (pin "5") (pinfunction "G2_5") (pintype "passive"))
      (node (ref "Q21") (pin "6") (pinfunction "D1_6") (pintype "passive"))
      (node (ref "R90") (pin "2") (pinfunction "2_2") (pintype "passive"))
    )
    (net (code "51") (name "Net-(Q21B-D2)") (class "Default")
      (node (ref "FB2") (pin "2") (pinfunction "2_2") (pintype "passive"))
      (node (ref "Q21") (pin "3") (pinfunction "D2_3") (pintype "passive"))
    )
    (net (code "52") (name "Net-(Q25B-D2)") (class "Default")
      (node (ref "Q25") (pin "3") (pinfunction "D2_3") (pintype "passive"))
      (node (ref "R127") (pin "2") (pinfunction "2_2") (pintype "passive"))
      (node (ref "U23") (pin "26") (pinfunction "RESET_N_26") (pintype "passive"))
    )
    (net (code "53") (name "Net-(Q25B-G2)") (class "Default")
      (node (ref "NC11") (pin "1") (pinfunction "1_1") (pintype "passive"))
      (node (ref "Q25") (pin "5") (pinfunction "G2_5") (pintype "passive"))
    )
    (net (code "54") (name "Net-(U6-DCD0)") (class "Default")
      (node (ref "R30") (pin "2") (pinfunction "2_2") (pintype "passive"))
      (node (ref "U6") (pin "51") (pinfunction "DCD0_51") (pintype "input"))
    )
    (net (code "55") (name "Net-(U6-DCD1)") (class "Default")
      (node (ref "R27") (pin "2") (pinfunction "2_2") (pintype "passive"))
      (node (ref "U6") (pin "43") (pinfunction "DCD1_43") (pintype "input"))
    )
    (net (code "56") (name "Net-(U6-DCD2)") (class "Default")
      (node (ref "R40") (pin "2") (pinfunction "2_2") (pintype "passive"))
      (node (ref "U6") (pin "12") (pinfunction "DCD2_12") (pintype "input"))
    )
    (net (code "57") (name "Net-(U6-DCD3)") (class "Default")
      (node (ref "R42") (pin "2") (pinfunction "2_2") (pintype "passive"))
      (node (ref "U6") (pin "8") (pinfunction "DCD3_8") (pintype "input"))
    )
    (net (code "58") (name "Net-(U6-DSR0)") (class "Default")
      (node (ref "R29") (pin "2") (pinfunction "2_2") (pintype "passive"))
      (node (ref "U6") (pin "52") (pinfunction "DSR0_52") (pintype "input"))
    )
    (net (code "59") (name "Net-(U6-DSR1)") (class "Default")
      (node (ref "R26") (pin "2") (pinfunction "2_2") (pintype "passive"))
      (node (ref "U6") (pin "44") (pinfunction "DSR1_44") (pintype "input"))
    )
    (net (code "60") (name "Net-(U6-DSR3)") (class "Default")
      (node (ref "R41") (pin "2") (pinfunction "2_2") (pintype "passive"))
      (node (ref "U6") (pin "9") (pinfunction "DSR3_9") (pintype "input"))
    )
    (net (code "61") (name "Net-(U23-CRFILT)") (class "Default")
      (node (ref "C89") (pin "1") (pinfunction "1_1") (pintype "passive"))
      (node (ref "U23") (pin "14") (pinfunction "CRFILT_14") (pintype "passive"))
    )
    (net (code "62") (name "Net-(U23-HS_IND{slash}CFG_SEL1)") (class "Default")
      (node (ref "R110") (pin "1") (pinfunction "1_1") (pintype "passive"))
      (node (ref "U23") (pin "25") (pinfunction "HS_IND/CFG_SEL1_25") (pintype "passive"))
    )
    (net (code "63") (name "Net-(U23-OCS_N1)") (class "Default")
      (node (ref "R91") (pin "1") (pinfunction "1_1") (pintype "passive"))
      (node (ref "U23") (pin "13") (pinfunction "OCS_N1_13") (pintype "passive"))
    )
    (net (code "64") (name "Net-(U23-OCS_N2)") (class "Default")
      (node (ref "R94") (pin "2") (pinfunction "2_2") (pintype "passive"))
      (node (ref "U23") (pin "17") (pinfunction "OCS_N2_17") (pintype "passive"))
    )
    (net (code "65") (name "Net-(U23-OCS_N3)") (class "Default")
      (node (ref "R99") (pin "2") (pinfunction "2_2") (pintype "passive"))
      (node (ref "U23") (pin "19") (pinfunction "OCS_N3_19") (pintype "passive"))
    )
    (net (code "66") (name "Net-(U23-PLLFILT)") (class "Default")
      (node (ref "C90") (pin "1") (pinfunction "1_1") (pintype "passive"))
      (node (ref "U23") (pin "34") (pinfunction "PLLFILT_34") (pintype "passive"))
    )
    (net (code "67") (name "Net-(U23-PRTPWR1{slash}BC_EN1)") (class "Default")
      (node (ref "R87") (pin "2") (pinfunction "2_2") (pintype "passive"))
      (node (ref "R88") (pin "1") (pinfunction "1_1") (pintype "passive"))
      (node (ref "U23") (pin "12") (pinfunction "PRTPWR1/BC_EN1_12") (pintype "passive"))
    )
    (net (code "68") (name "Net-(U23-PRTPWR2{slash}BC_EN2)") (class "Default")
      (node (ref "R92") (pin "2") (pinfunction "2_2") (pintype "passive"))
      (node (ref "R93") (pin "1") (pinfunction "1_1") (pintype "passive"))
      (node (ref "U23") (pin "16") (pinfunction "PRTPWR2/BC_EN2_16") (pintype "passive"))
    )
    (net (code "69") (name "Net-(U23-PRTPWR3{slash}BC_EN3)") (class "Default")
      (node (ref "R97") (pin "2") (pinfunction "2_2") (pintype "passive"))
      (node (ref "R98") (pin "1") (pinfunction "1_1") (pintype "passive"))
      (node (ref "U23") (pin "18") (pinfunction "PRTPWR3/BC_EN3_18") (pintype "passive"))
    )
    (net (code "70") (name "Net-(U23-RBIAS)") (class "Default")
      (node (ref "R89") (pin "2") (pinfunction "2_2") (pintype "passive"))
      (node (ref "U23") (pin "35") (pinfunction "RBIAS_35") (pintype "passive"))
    )
    (net (code "71") (name "Net-(U23-SCL{slash}SMBCLK{slash}CFG_SEL0)") (class "Default")
      (node (ref "R106") (pin "1") (pinfunction "1_1") (pintype "passive"))
      (node (ref "U23") (pin "24") (pinfunction "SCL/SMBCLK/CFG_SEL0_24") (pintype "passive"))
    )
    (net (code "72") (name "Net-(U23-SDA{slash}SMBDATA{slash}NON_REM1)") (class "Default")
      (node (ref "R95") (pin "2") (pinfunction "2_2") (pintype "passive"))
      (node (ref "U23") (pin "22") (pinfunction "SDA/SMBDATA/NON_REM1_22") (pintype "passive"))
    )
    (net (code "73") (name "Net-(U23-SUSP_IND{slash}LOCAL_PWR{slash}NON_REM0)") (class "Default")
      (node (ref "R102") (pin "2") (pinfunction "2_2") (pintype "passive"))
      (node (ref "U23") (pin "28") (pinfunction "SUSP_IND/LOCAL_PWR/NON_REM0_28") (pintype "passive"))
    )
    (net (code "74") (name "Net-(U23-VBUS_DET)") (class "Default")
      (node (ref "R100") (pin "2") (pinfunction "2_2") (pintype "passive"))
      (node (ref "R101") (pin "1") (pinfunction "1_1") (pintype "passive"))
      (node (ref "U23") (pin "27") (pinfunction "VBUS_DET_27") (pintype "passive"))
    )
    (net (code "75") (name "Net-(U23-XTALIN_CLKIN)") (class "Default")
      (node (ref "C88") (pin "1") (pinfunction "1_1") (pintype "passive"))
      (node (ref "U23") (pin "33") (pinfunction "XTALIN_CLKIN_33") (pintype "passive"))
      (node (ref "X2") (pin "3") (pintype "passive"))
    )
    (net (code "76") (name "Net-(U23-XTALOUT)") (class "Default")
      (node (ref "C102") (pin "1") (pinfunction "1_1") (pintype "passive"))
      (node (ref "U23") (pin "32") (pinfunction "XTALOUT_32") (pintype "passive"))
      (node (ref "X2") (pin "1") (pintype "passive"))
    )
    (net (code "77") (name "VBUS") (class "Default")
      (node (ref "C132") (pin "2") (pinfunction "2_2") (pintype "passive"))
      (node (ref "C43") (pin "1") (pinfunction "1_1") (pintype "passive"))
      (node (ref "C44") (pin "1") (pinfunction "1_1") (pintype "passive"))
      (node (ref "D28") (pin "6") (pinfunction "Vcc_6") (pintype "power_in"))
      (node (ref "FB9") (pin "2") (pinfunction "2_2") (pintype "passive"))
      (node (ref "Q21") (pin "2") (pinfunction "G1_2") (pintype "passive"))
      (node (ref "R100") (pin "1") (pinfunction "1_1") (pintype "passive"))
      (node (ref "TP49") (pin "1") (pintype "passive"))
      (node (ref "U6") (pin "60") (pinfunction "VREGIN_60") (pintype "power_in"))
      (node (ref "U6") (pin "61") (pinfunction "VBUS_61") (pintype "power_in"))
    )
    (net (code "78") (name "unconnected-(D28-IO3-Pad4)") (class "Default")
      (node (ref "D28") (pin "4") (pinfunction "IO3_4") (pintype "passive+no_connect"))
    )
    (net (code "79") (name "unconnected-(D28-NC-Pad5)") (class "Default")
      (node (ref "D28") (pin "5") (pinfunction "NC_5") (pintype "passive+no_connect"))
    )
    (net (code "80") (name "unconnected-(J12-ID-Pad4)") (class "Default")
      (node (ref "J12") (pin "4") (pinfunction "ID_4") (pintype "passive+no_connect"))
    )
    (net (code "81") (name "unconnected-(Q14A-D1-Pad6)") (class "Default")
      (node (ref "Q14") (pin "6") (pinfunction "D1_6") (pintype "passive+no_connect"))
    )
    (net (code "82") (name "unconnected-(U6-CTS3-Pad5)") (class "Default")
      (node (ref "U6") (pin "5") (pinfunction "CTS3_5") (pintype "input+no_connect"))
    )
    (net (code "83") (name "unconnected-(U6-DTR0-Pad53)") (class "Default")
      (node (ref "U6") (pin "53") (pinfunction "DTR0_53") (pintype "output+no_connect"))
    )
    (net (code "84") (name "unconnected-(U6-DTR1-Pad45)") (class "Default")
      (node (ref "U6") (pin "45") (pinfunction "DTR1_45") (pintype "output+no_connect"))
    )
    (net (code "85") (name "unconnected-(U6-DTR3-Pad10)") (class "Default")
      (node (ref "U6") (pin "10") (pinfunction "DTR3_10") (pintype "output+no_connect"))
    )
    (net (code "86") (name "unconnected-(U6-GPIO.0-Pad41)") (class "Default")
      (node (ref "U6") (pin "41") (pinfunction "GPIO.0_41") (pintype "bidirectional+no_connect"))
    )
    (net (code "87") (name "unconnected-(U6-GPIO.1-Pad40)") (class "Default")
      (node (ref "U6") (pin "40") (pinfunction "GPIO.1_40") (pintype "bidirectional+no_connect"))
    )
    (net (code "88") (name "unconnected-(U6-GPIO.2-Pad38)") (class "Default")
      (node (ref "U6") (pin "38") (pinfunction "GPIO.2_38") (pintype "bidirectional+no_connect"))
    )
    (net (code "89") (name "unconnected-(U6-GPIO.3-Pad37)") (class "Default")
      (node (ref "U6") (pin "37") (pinfunction "GPIO.3_37") (pintype "bidirectional+no_connect"))
    )
    (net (code "90") (name "unconnected-(U6-GPIO.4-Pad34)") (class "Default")
      (node (ref "U6") (pin "34") (pinfunction "GPIO.4_34") (pintype "bidirectional+no_connect"))
    )
    (net (code "91") (name "unconnected-(U6-GPIO.5-Pad33)") (class "Default")
      (node (ref "U6") (pin "33") (pinfunction "GPIO.5_33") (pintype "bidirectional+no_connect"))
    )
    (net (code "92") (name "unconnected-(U6-GPIO.6-Pad32)") (class "Default")
      (node (ref "U6") (pin "32") (pinfunction "GPIO.6_32") (pintype "bidirectional+no_connect"))
    )
    (net (code "93") (name "unconnected-(U6-GPIO.7-Pad31)") (class "Default")
      (node (ref "U6") (pin "31") (pinfunction "GPIO.7_31") (pintype "bidirectional+no_connect"))
    )
    (net (code "94") (name "unconnected-(U6-GPIO.8-Pad30)") (class "Default")
      (node (ref "U6") (pin "30") (pinfunction "GPIO.8_30") (pintype "bidirectional+no_connect"))
    )
    (net (code "95") (name "unconnected-(U6-GPIO.9-Pad29)") (class "Default")
      (node (ref "U6") (pin "29") (pinfunction "GPIO.9_29") (pintype "bidirectional+no_connect"))
    )
    (net (code "96") (name "unconnected-(U6-GPIO.10-Pad28)") (class "Default")
      (node (ref "U6") (pin "28") (pinfunction "GPIO.10_28") (pintype "bidirectional+no_connect"))
    )
    (net (code "97") (name "unconnected-(U6-GPIO.11-Pad27)") (class "Default")
      (node (ref "U6") (pin "27") (pinfunction "GPIO.11_27") (pintype "bidirectional+no_connect"))
    )
    (net (code "98") (name "unconnected-(U6-GPIO.12-Pad26)") (class "Default")
      (node (ref "U6") (pin "26") (pinfunction "GPIO.12_26") (pintype "bidirectional+no_connect"))
    )
    (net (code "99") (name "unconnected-(U6-GPIO.13-Pad23)") (class "Default")
      (node (ref "U6") (pin "23") (pinfunction "GPIO.13_23") (pintype "bidirectional+no_connect"))
    )
    (net (code "100") (name "unconnected-(U6-GPIO.14-Pad22)") (class "Default")
      (node (ref "U6") (pin "22") (pinfunction "GPIO.14_22") (pintype "bidirectional+no_connect"))
    )
    (net (code "101") (name "unconnected-(U6-GPIO.15-Pad21)") (class "Default")
      (node (ref "U6") (pin "21") (pinfunction "GPIO.15_21") (pintype "bidirectional+no_connect"))
    )
    (net (code "102") (name "unconnected-(U6-RI0-Pad50)") (class "Default")
      (node (ref "U6") (pin "50") (pinfunction "RI0_50") (pintype "input+no_connect"))
    )
    (net (code "103") (name "unconnected-(U6-RI1-Pad42)") (class "Default")
      (node (ref "U6") (pin "42") (pinfunction "RI1_42") (pintype "input+no_connect"))
    )
    (net (code "104") (name "unconnected-(U6-RI2-Pad11)") (class "Default")
      (node (ref "U6") (pin "11") (pinfunction "RI2_11") (pintype "input+no_connect"))
    )
    (net (code "105") (name "unconnected-(U6-RI3-Pad7)") (class "Default")
      (node (ref "U6") (pin "7") (pinfunction "RI3_7") (pintype "input+no_connect"))
    )
    (net (code "106") (name "unconnected-(U6-RTS3-Pad6)") (class "Default")
      (node (ref "U6") (pin "6") (pinfunction "RTS3_6") (pintype "output+no_connect"))
    )
    (net (code "107") (name "unconnected-(U6-SUSPEND-Pad20)") (class "Default")
      (node (ref "U6") (pin "20") (pinfunction "SUSPEND_20") (pintype "output+no_connect"))
    )
    (net (code "108") (name "unconnected-(U6-~{SUSPEND}-Pad19)") (class "Default")
      (node (ref "U6") (pin "19") (pinfunction "~{SUSPEND}_19") (pintype "output+no_connect"))
    )
    (net (code "109") (name "unconnected-(U23-NC-Pad8)") (class "Default")
      (node (ref "U23") (pin "8") (pinfunction "NC_8") (pintype "passive+no_connect"))
    )
    (net (code "110") (name "unconnected-(U23-NC-Pad9)") (class "Default")
      (node (ref "U23") (pin "9") (pinfunction "NC_9") (pintype "passive+no_connect"))
    )
    (net (code "111") (name "unconnected-(U23-NC-Pad20)") (class "Default")
      (node (ref "U23") (pin "20") (pinfunction "NC_20") (pintype "passive+no_connect"))
    )
    (net (code "112") (name "unconnected-(U23-NC-Pad21)") (class "Default")
      (node (ref "U23") (pin "21") (pinfunction "NC_21") (pintype "passive+no_connect"))
    )
    (net (code "113") (name "unconnected-(U23-TEST-Pad11)") (class "Default")
      (node (ref "U23") (pin "11") (pinfunction "TEST_11") (pintype "passive+no_connect"))
    )
  )
)
